# RPlan_LB.net
KiCad netlist of a schematic drawn in Altium Designer
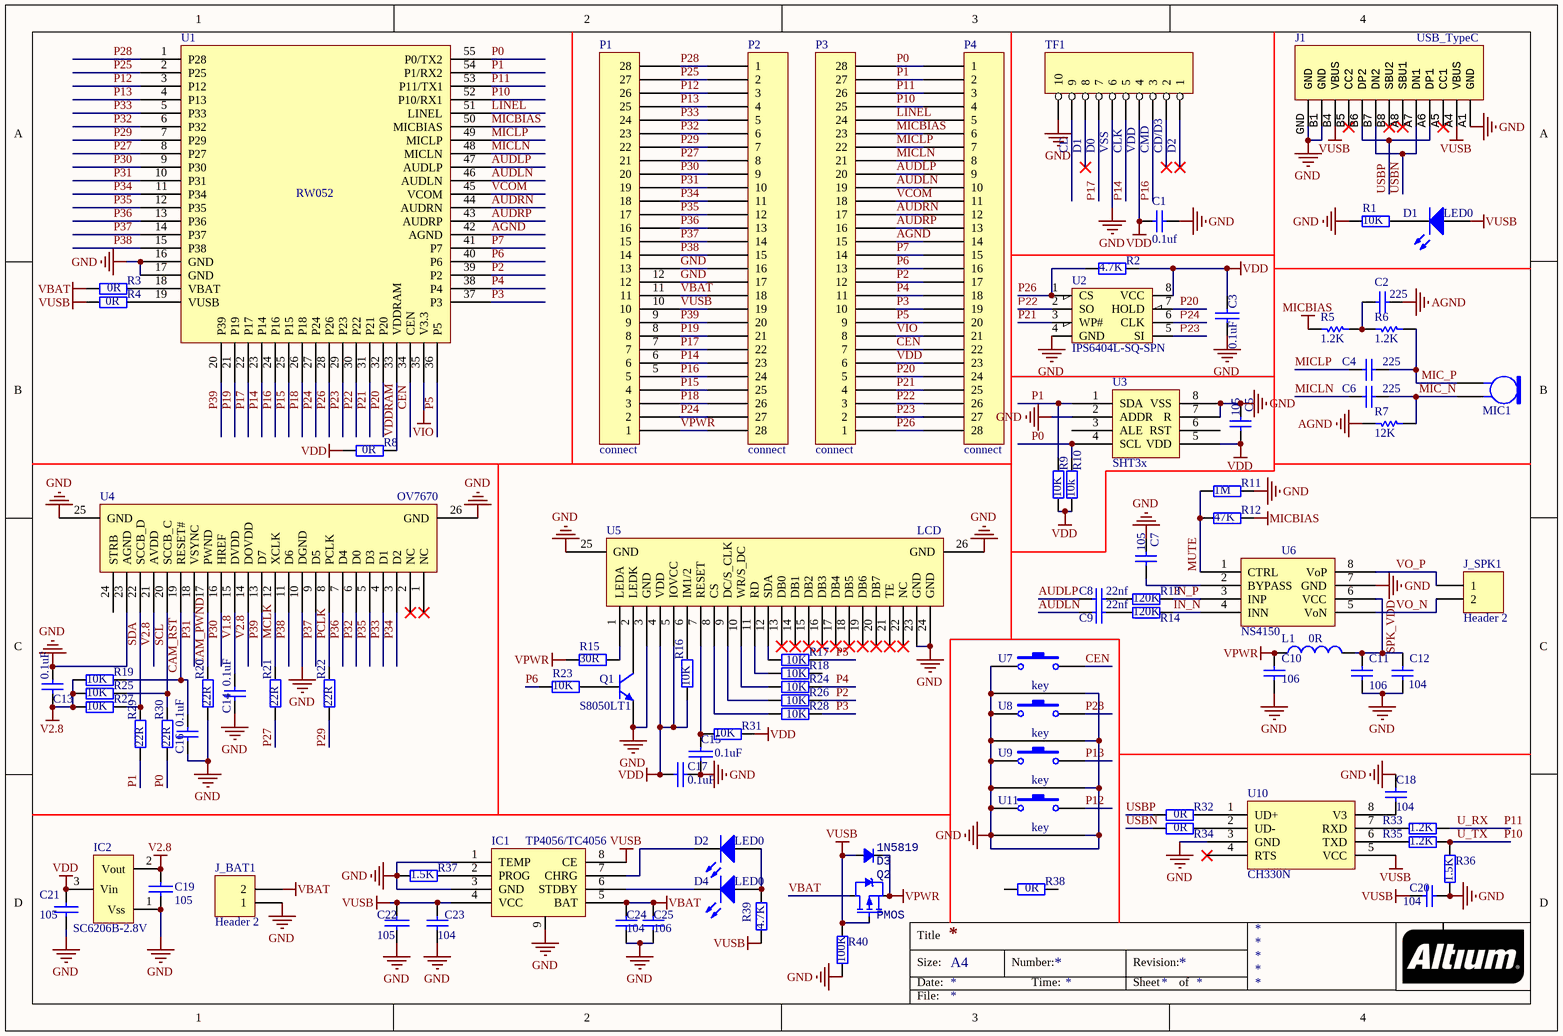
[diagram p0: RPlan_LB.SchDoc]

(export (version "E")
  (design (tool "Eeschema 10.0.6"))
  (components
    (comp (ref "C1")
      (value "0.1uf")
      (footprint "0603C")
      (description "Capacitor")
      (fields (field (name "PUBLISHER") "Altium Limited"))
      (libsource (lib "Miscellaneous Devices") (part "Cap"))
    )
    (comp (ref "C2") (value "225") (footprint "0603C") (libsource (lib "Miscellaneous Gallery") (part "CAP")))
    (comp (ref "C3")
      (value "0.1uF")
      (footprint "0603C")
      (description "Capacitor")
      (libsource (lib "Schlib") (part "CAP"))
    )
    (comp (ref "C4") (value "225") (footprint "0603C") (libsource (lib "Miscellaneous Gallery") (part "CAP")))
    (comp (ref "C5")
      (value "105")
      (footprint "0603C")
      (description "Capacitor")
      (fields (field (name "PUBLISHER") "Altium Limited"))
      (libsource (lib "Miscellaneous Devices") (part "Cap"))
    )
    (comp (ref "C6") (value "225") (footprint "0603C") (libsource (lib "Miscellaneous Gallery") (part "CAP")))
    (comp (ref "C7")
      (value "105")
      (footprint "0603C")
      (description "Capacitor")
      (fields (field (name "PUBLISHER") "Altium Limited"))
      (libsource (lib "Miscellaneous Devices") (part "Cap"))
    )
    (comp (ref "C8")
      (value "22nf")
      (footprint "0603C")
      (description "Capacitor")
      (fields (field (name "PUBLISHER") "Altium Limited"))
      (libsource (lib "") (part "Cap_1"))
    )
    (comp (ref "C9")
      (value "22nf")
      (footprint "0603C")
      (description "Capacitor")
      (fields (field (name "PUBLISHER") "Altium Limited"))
      (libsource (lib "Miscellaneous Devices") (part "Cap"))
    )
    (comp (ref "C10")
      (value "106")
      (footprint "0603C")
      (description "Capacitor")
      (fields (field (name "PUBLISHER") "Altium Limited"))
      (libsource (lib "Miscellaneous Devices") (part "Cap"))
    )
    (comp (ref "C11")
      (value "106")
      (footprint "0603C")
      (description "Capacitor")
      (fields (field (name "PUBLISHER") "Altium Limited"))
      (libsource (lib "Miscellaneous Devices") (part "Cap"))
    )
    (comp (ref "C12")
      (value "104")
      (footprint "0603C")
      (libsource (lib "Miscellaneous Gallery") (part "CAP"))
    )
    (comp (ref "C13")
      (value "0.1uF")
      (footprint "0603C")
      (description "Capacitor")
      (fields (field (name "PUBLISHER") "Altium Limited"))
      (libsource (lib "") (part "Cap_1"))
    )
    (comp (ref "C14")
      (value "0.1uF")
      (footprint "0603C")
      (description "Capacitor")
      (fields (field (name "PUBLISHER") "Altium Limited"))
      (libsource (lib "") (part "Cap_1"))
    )
    (comp (ref "C15")
      (value "0.1uF")
      (footprint "0603C")
      (description "Capacitor")
      (libsource (lib "*") (part "CAP"))
    )
    (comp (ref "C16")
      (value "0.1uF")
      (footprint "0603C")
      (description "Capacitor")
      (fields (field (name "PUBLISHER") "Altium Limited"))
      (libsource (lib "") (part "Cap_1"))
    )
    (comp (ref "C17")
      (value "0.1uF")
      (footprint "0603C")
      (description "Capacitor")
      (libsource (lib "*") (part "CAP"))
    )
    (comp (ref "C18")
      (value "104")
      (footprint "0603C")
      (description "Capacitor")
      (fields (field (name "PUBLISHER") "Altium Limited"))
      (libsource (lib "Miscellaneous Devices") (part "Cap"))
    )
    (comp (ref "C19")
      (value "105")
      (footprint "0603C")
      (description "Capacitor")
      (libsource (lib "*") (part "CAP"))
    )
    (comp (ref "C20")
      (value "104")
      (footprint "0603C")
      (description "Capacitor")
      (fields (field (name "PUBLISHER") "Altium Limited"))
      (libsource (lib "Miscellaneous Devices") (part "Cap"))
    )
    (comp (ref "C21")
      (value "105")
      (footprint "0603C")
      (description "Capacitor")
      (libsource (lib "*") (part "CAP"))
    )
    (comp (ref "C22")
      (value "105")
      (footprint "0603C")
      (description "Capacitor")
      (libsource (lib "Schlib") (part "CAP"))
    )
    (comp (ref "C23")
      (value "104")
      (footprint "0603C")
      (description "Capacitor")
      (fields (field (name "PUBLISHER") "Altium Limited"))
      (libsource (lib "Miscellaneous Devices") (part "Cap"))
    )
    (comp (ref "C24")
      (value "104")
      (footprint "0603C")
      (description "Capacitor")
      (fields (field (name "PUBLISHER") "Altium Limited"))
      (libsource (lib "Miscellaneous Devices") (part "Cap"))
    )
    (comp (ref "C25")
      (value "106")
      (footprint "0603C")
      (description "Capacitor")
      (fields (field (name "PUBLISHER") "Altium Limited"))
      (libsource (lib "Miscellaneous Devices") (part "Cap"))
    )
    (comp (ref "D1")
      (value "LED0")
      (footprint "0603_LED_R")
      (description "Typical INFRARED GaAs LED")
      (fields (field (name "PUBLISHER") "Altium Limited"))
      (libsource (lib "Miscellaneous Devices") (part "LED0"))
    )
    (comp (ref "D2")
      (value "LED0")
      (footprint "0603_LED_R")
      (description "Typical INFRARED GaAs LED")
      (fields (field (name "PUBLISHER") "Altium Limited"))
      (libsource (lib "Miscellaneous Devices") (part "LED0"))
    )
    (comp (ref "D3")
      (value "1N5819")
      (footprint "SOD-323")
      (description "Diode")
      (libsource (lib "Integrated_Library") (part "Diode_SOD123"))
    )
    (comp (ref "D4")
      (value "LED0")
      (footprint "0603_LED_G")
      (description "Typical INFRARED GaAs LED")
      (fields (field (name "PUBLISHER") "Altium Limited"))
      (libsource (lib "Miscellaneous Devices") (part "LED0"))
    )
    (comp (ref "IC1")
      (value "TP4056/TC4056")
      (footprint "SOP8_150mil")
      (libsource (lib "TP4056") (part "4056"))
    )
    (comp (ref "IC2")
      (value "SC6206B-2.8V")
      (footprint "SOT-23-3")
      (description "SC6206B-3V")
      (libsource (lib "Schlib") (part "ME6206A33M3G"))
    )
    (comp (ref "J1")
      (value "USB_TypeC")
      (footprint "USB_TypeC")
      (description "USB")
      (libsource (lib "SCH_USB") (part "USB_TypeC"))
    )
    (comp (ref "J_BAT1")
      (value "Header 2")
      (footprint "BAT")
      (description "Header, 2-Pin")
      (fields (field (name "PUBLISHER") "Altium Limited"))
      (libsource (lib "Miscellaneous Connectors") (part "Header 2"))
    )
    (comp (ref "J_SPK1")
      (value "Header 2")
      (footprint "MIC_4015_DIP")
      (description "Header, 2-Pin")
      (fields (field (name "PUBLISHER") "Altium Limited"))
      (libsource (lib "") (part "Header 2_1"))
    )
    (comp (ref "L1")
      (value "0R")
      (footprint "0603C")
      (description "GZ1608D121TF")
      (fields (field (name "PUBLISHER") "Altium Limited"))
      (libsource (lib "Miscellaneous Devices") (part "Inductor"))
    )
    (comp (ref "MIC1")
      (value "MIC")
      (footprint "MIC_4015_DIP")
      (libsource (lib "Miscellaneous Gallery") (part "MIC"))
    )
    (comp (ref "P1") (value "connect") (footprint "CONNECT2") (libsource (lib "") (part "connect_1")))
    (comp (ref "P2") (value "connect") (footprint "CONNECT") (libsource (lib "") (part "connect_2")))
    (comp (ref "P3") (value "connect") (footprint "CONNECT") (libsource (lib "RPlan_LB") (part "connect")))
    (comp (ref "P4") (value "connect") (footprint "CONNECT2") (libsource (lib "") (part "connect_2")))
    (comp (ref "Q1")
      (value "S8050LT1")
      (footprint "SOT-23-3")
      (description "NPN Bipolar Transistor")
      (fields (field (name "PUBLISHER") "Altium Limited"))
      (libsource (lib "Schlib") (part "NPN"))
    )
    (comp (ref "Q2")
      (value "PMOS")
      (footprint "SOT-23-3")
      (description "MOSFET")
      (libsource (lib "SCH_Active") (part "MOSFET_P_SOT23"))
    )
    (comp (ref "R1")
      (value "10K")
      (footprint "0603C")
      (description "RES")
      (libsource (lib "") (part "RES_1"))
    )
    (comp (ref "R2")
      (value "4.7K")
      (footprint "0603C")
      (description "RES")
      (libsource (lib "") (part "RES_2"))
    )
    (comp (ref "R3")
      (value "0R")
      (footprint "0603C")
      (description "Resistor")
      (fields (field (name "PUBLISHER") "Altium Limited"))
      (libsource (lib "") (part "Res2_1"))
    )
    (comp (ref "R4")
      (value "0R")
      (footprint "0603C")
      (description "Resistor")
      (fields (field (name "PUBLISHER") "Altium Limited"))
      (libsource (lib "") (part "Res2_1"))
    )
    (comp (ref "R5")
      (value "1.2K")
      (footprint "0603C")
      (libsource (lib "Miscellaneous Gallery") (part "Res"))
    )
    (comp (ref "R6") (value "1.2K") (footprint "0603C") (libsource (lib "") (part "Res_1")))
    (comp (ref "R7") (value "12K") (footprint "0603C") (libsource (lib "Miscellaneous Gallery") (part "Res")))
    (comp (ref "R8")
      (value "0R")
      (footprint "0603C")
      (description "Resistor")
      (fields (field (name "PUBLISHER") "Altium Limited"))
      (libsource (lib "") (part "Res2_1"))
    )
    (comp (ref "R9")
      (value "10K")
      (footprint "0603C")
      (description "RES")
      (libsource (lib "Schlib") (part "RES"))
    )
    (comp (ref "R10")
      (value "10k")
      (footprint "0603C")
      (description "RES")
      (libsource (lib "Schlib") (part "RES"))
    )
    (comp (ref "R11")
      (value "1M")
      (footprint "0603C")
      (description "RES")
      (libsource (lib "") (part "RES_1"))
    )
    (comp (ref "R12")
      (value "47K")
      (footprint "0603C")
      (description "RES")
      (libsource (lib "") (part "RES_1"))
    )
    (comp (ref "R13")
      (value "120K")
      (footprint "0603C")
      (description "RES")
      (libsource (lib "") (part "RES_2"))
    )
    (comp (ref "R14")
      (value "120K")
      (footprint "0603C")
      (description "RES")
      (libsource (lib "") (part "RES_1"))
    )
    (comp (ref "R15")
      (value "30R")
      (footprint "0603C")
      (description "Resistor")
      (fields (field (name "PUBLISHER") "Altium Limited"))
      (libsource (lib "") (part "Res2_1"))
    )
    (comp (ref "R16")
      (value "10K")
      (footprint "0603C")
      (description "Resistor")
      (fields (field (name "PUBLISHER") "Altium Limited"))
      (libsource (lib "") (part "Res2_2"))
    )
    (comp (ref "R17")
      (value "10K")
      (footprint "0603C")
      (description "Resistor")
      (fields (field (name "PUBLISHER") "Altium Limited"))
      (libsource (lib "") (part "Res2_1"))
    )
    (comp (ref "R18")
      (value "10K")
      (footprint "0603C")
      (description "Resistor")
      (fields (field (name "PUBLISHER") "Altium Limited"))
      (libsource (lib "") (part "Res2_1"))
    )
    (comp (ref "R19")
      (value "10K")
      (footprint "0603C")
      (description "Resistor")
      (fields (field (name "PUBLISHER") "Altium Limited"))
      (libsource (lib "") (part "Res2_1"))
    )
    (comp (ref "R20")
      (value "22R")
      (footprint "0603C")
      (description "Resistor")
      (fields (field (name "PUBLISHER") "Altium Limited"))
      (libsource (lib "Miscellaneous Devices") (part "Res2"))
    )
    (comp (ref "R21")
      (value "22R")
      (footprint "0603C")
      (description "Resistor")
      (fields (field (name "PUBLISHER") "Altium Limited"))
      (libsource (lib "Miscellaneous Devices") (part "Res2"))
    )
    (comp (ref "R22")
      (value "22R")
      (footprint "0603C")
      (description "Resistor")
      (fields (field (name "PUBLISHER") "Altium Limited"))
      (libsource (lib "") (part "Res2_2"))
    )
    (comp (ref "R23")
      (value "10K")
      (footprint "0603C")
      (description "Resistor")
      (fields (field (name "PUBLISHER") "Altium Limited"))
      (libsource (lib "") (part "Res2_1"))
    )
    (comp (ref "R24")
      (value "10K")
      (footprint "0603C")
      (description "Resistor")
      (fields (field (name "PUBLISHER") "Altium Limited"))
      (libsource (lib "") (part "Res2_1"))
    )
    (comp (ref "R25")
      (value "10K")
      (footprint "0603C")
      (description "Resistor")
      (fields (field (name "PUBLISHER") "Altium Limited"))
      (libsource (lib "") (part "Res2_1"))
    )
    (comp (ref "R26")
      (value "10K")
      (footprint "0603C")
      (description "Resistor")
      (fields (field (name "PUBLISHER") "Altium Limited"))
      (libsource (lib "") (part "Res2_1"))
    )
    (comp (ref "R27")
      (value "10K")
      (footprint "0603C")
      (description "Resistor")
      (fields (field (name "PUBLISHER") "Altium Limited"))
      (libsource (lib "") (part "Res2_1"))
    )
    (comp (ref "R28")
      (value "10K")
      (footprint "0603C")
      (description "Resistor")
      (fields (field (name "PUBLISHER") "Altium Limited"))
      (libsource (lib "") (part "Res2_1"))
    )
    (comp (ref "R29")
      (value "22R")
      (footprint "0603C")
      (description "Resistor")
      (fields (field (name "PUBLISHER") "Altium Limited"))
      (libsource (lib "Miscellaneous Devices") (part "Res2"))
    )
    (comp (ref "R30")
      (value "22R")
      (footprint "0603C")
      (description "Resistor")
      (fields (field (name "PUBLISHER") "Altium Limited"))
      (libsource (lib "Miscellaneous Devices") (part "Res2"))
    )
    (comp (ref "R31")
      (value "10K")
      (footprint "0603C")
      (description "Resistor")
      (fields (field (name "PUBLISHER") "Altium Limited"))
      (libsource (lib "") (part "Res2_1"))
    )
    (comp (ref "R32")
      (value "0R")
      (footprint "0603C")
      (description "RES")
      (libsource (lib "") (part "RES_2"))
    )
    (comp (ref "R33")
      (value "1.2K")
      (footprint "0603C")
      (description "RES")
      (libsource (lib "") (part "RES_2"))
    )
    (comp (ref "R34")
      (value "0R")
      (footprint "0603C")
      (description "RES")
      (libsource (lib "") (part "RES_2"))
    )
    (comp (ref "R35")
      (value "1.2K")
      (footprint "0603C")
      (description "RES")
      (libsource (lib "") (part "RES_2"))
    )
    (comp (ref "R36")
      (value "1.5K")
      (footprint "0603C")
      (description "RES")
      (libsource (lib "") (part "RES_3"))
    )
    (comp (ref "R37")
      (value "1.5K")
      (footprint "0603C")
      (description "RES")
      (libsource (lib "") (part "RES_2"))
    )
    (comp (ref "R38")
      (value "0R")
      (footprint "LCD_13")
      (description "RES")
      (libsource (lib "") (part "RES_2"))
    )
    (comp (ref "R39")
      (value "4.7K")
      (footprint "0603C")
      (description "RES")
      (libsource (lib "Schlib") (part "RES"))
    )
    (comp (ref "R40")
      (value "100K")
      (footprint "0603C")
      (description "RES")
      (libsource (lib "") (part "RES_3"))
    )
    (comp (ref "TF1") (value "~") (footprint "TF1") (libsource (lib "*") (part "HEADER 10")))
    (comp (ref "U1") (value "RW052") (footprint "RW052") (libsource (lib "RW052") (part "RW052")))
    (comp (ref "U2")
      (value "IPS6404L-SQ-SPN")
      (footprint "SOP8_150mil")
      (libsource (lib "Schlib") (part "W25X16"))
    )
    (comp (ref "U3") (value "SHT3x") (footprint "SHT3X") (libsource (lib "RPlan_LB") (part "SHT3x")))
    (comp (ref "U4")
      (value "OV7670")
      (footprint "FPC_0.5_24P_L")
      (libsource (lib "RPlan_LB") (part "OV7670"))
    )
    (comp (ref "U5") (value "LCD") (footprint "FPC_0.5_24P_LF") (libsource (lib "RPlan_LB") (part "LCD")))
    (comp (ref "U6") (value "NS4150") (footprint "SOP8_150mil") (libsource (lib "NS4150") (part "NS4150")))
    (comp (ref "U7") (value "key") (footprint "KEY") (libsource (lib "RPlan_LB") (part "key")))
    (comp (ref "U8") (value "key") (footprint "KEY") (libsource (lib "RPlan_LB") (part "key")))
    (comp (ref "U9") (value "key") (footprint "KEY") (libsource (lib "RPlan_LB") (part "key")))
    (comp (ref "U10")
      (value "CH330N")
      (footprint "SOP8_150mil")
      (libsource (lib "CH330_340") (part "CH330N"))
    )
    (comp (ref "U11") (value "key") (footprint "KEY") (libsource (lib "RPlan_LB") (part "key")))
  )
  (nets
    (net (code "1") (name "/AUDLN") (class "Default")
      (node (ref "C9") (pin "2") (pinfunction "2_2") (pintype "passive"))
      (node (ref "P3") (pin "19") (pinfunction "19_19") (pintype "passive"))
      (node (ref "P4") (pin "10") (pinfunction "10_10") (pintype "passive"))
      (node (ref "U1") (pin "46") (pinfunction "AUDLN_46") (pintype "passive"))
    )
    (net (code "2") (name "/AUDLP") (class "Default")
      (node (ref "C8") (pin "2") (pinfunction "2_2") (pintype "passive"))
      (node (ref "P3") (pin "20") (pinfunction "20_20") (pintype "passive"))
      (node (ref "P4") (pin "9") (pinfunction "9_9") (pintype "passive"))
      (node (ref "U1") (pin "47") (pinfunction "AUDLP_47") (pintype "passive"))
    )
    (net (code "3") (name "/AUDRN") (class "Default")
      (node (ref "P3") (pin "17") (pinfunction "17_17") (pintype "passive"))
      (node (ref "P4") (pin "12") (pinfunction "12_12") (pintype "passive"))
      (node (ref "U1") (pin "44") (pinfunction "AUDRN_44") (pintype "passive"))
    )
    (net (code "4") (name "/AUDRP") (class "Default")
      (node (ref "P3") (pin "16") (pinfunction "16_16") (pintype "passive"))
      (node (ref "P4") (pin "13") (pinfunction "13_13") (pintype "passive"))
      (node (ref "U1") (pin "43") (pinfunction "AUDRP_43") (pintype "passive"))
    )
    (net (code "5") (name "/CAM_PWND") (class "Default")
      (node (ref "R20") (pin "2") (pinfunction "2_2") (pintype "passive"))
      (node (ref "U4") (pin "17") (pinfunction "PWND_17") (pintype "passive"))
    )
    (net (code "6") (name "/CAM_RST") (class "Default")
      (node (ref "C16") (pin "2") (pinfunction "2_2") (pintype "passive"))
      (node (ref "R19") (pin "1") (pinfunction "1_1") (pintype "passive"))
      (node (ref "U4") (pin "19") (pinfunction "RESET#_19") (pintype "passive"))
    )
    (net (code "7") (name "/CEN") (class "Default")
      (node (ref "P3") (pin "7") (pinfunction "7_7") (pintype "passive"))
      (node (ref "P4") (pin "22") (pinfunction "22_22") (pintype "passive"))
      (node (ref "U1") (pin "34") (pinfunction "CEN_34") (pintype "passive"))
      (node (ref "U7") (pin "2") (pinfunction "2_2") (pintype "passive"))
    )
    (net (code "8") (name "/IN_N") (class "Default")
      (node (ref "R14") (pin "2") (pinfunction "2_2") (pintype "passive"))
      (node (ref "U6") (pin "4") (pinfunction "INN_4") (pintype "passive"))
    )
    (net (code "9") (name "/IN_P") (class "Default")
      (node (ref "R13") (pin "1") (pinfunction "1_1") (pintype "passive"))
      (node (ref "U6") (pin "3") (pinfunction "INP_3") (pintype "passive"))
    )
    (net (code "10") (name "/LINEL") (class "Default")
      (node (ref "P3") (pin "24") (pinfunction "24_24") (pintype "passive"))
      (node (ref "P4") (pin "5") (pinfunction "5_5") (pintype "passive"))
      (node (ref "U1") (pin "51") (pinfunction "LINEL_51") (pintype "passive"))
    )
    (net (code "11") (name "/MCLK") (class "Default")
      (node (ref "R21") (pin "2") (pinfunction "2_2") (pintype "passive"))
      (node (ref "U4") (pin "12") (pinfunction "XCLK_12") (pintype "passive"))
    )
    (net (code "12") (name "/MICLN") (class "Default")
      (node (ref "C6") (pin "2") (pinfunction "2_2") (pintype "passive"))
      (node (ref "P3") (pin "21") (pinfunction "21_21") (pintype "passive"))
      (node (ref "P4") (pin "8") (pinfunction "8_8") (pintype "passive"))
      (node (ref "U1") (pin "48") (pinfunction "MICLN_48") (pintype "passive"))
    )
    (net (code "13") (name "/MICLP") (class "Default")
      (node (ref "C4") (pin "2") (pinfunction "2_2") (pintype "passive"))
      (node (ref "P3") (pin "22") (pinfunction "22_22") (pintype "passive"))
      (node (ref "P4") (pin "7") (pinfunction "7_7") (pintype "passive"))
      (node (ref "U1") (pin "49") (pinfunction "MICLP_49") (pintype "passive"))
    )
    (net (code "14") (name "/MIC_N") (class "Default")
      (node (ref "C6") (pin "1") (pinfunction "1_1") (pintype "passive"))
      (node (ref "MIC1") (pin "2") (pinfunction "2_2") (pintype "passive"))
      (node (ref "R7") (pin "2") (pinfunction "2_2") (pintype "passive"))
    )
    (net (code "15") (name "/MIC_P") (class "Default")
      (node (ref "C4") (pin "1") (pinfunction "1_1") (pintype "passive"))
      (node (ref "MIC1") (pin "1") (pinfunction "1_1") (pintype "passive"))
      (node (ref "R6") (pin "1") (pinfunction "1_1") (pintype "passive"))
    )
    (net (code "16") (name "/MUTE") (class "Default")
      (node (ref "R11") (pin "1") (pinfunction "1_1") (pintype "passive"))
      (node (ref "R12") (pin "1") (pinfunction "1_1") (pintype "passive"))
      (node (ref "U6") (pin "1") (pinfunction "CTRL_1") (pintype "passive"))
    )
    (net (code "17") (name "/P0") (class "Default")
      (node (ref "P3") (pin "28") (pinfunction "28_28") (pintype "passive"))
      (node (ref "P4") (pin "1") (pinfunction "1_1") (pintype "passive"))
      (node (ref "R10") (pin "1") (pinfunction "1_1") (pintype "passive"))
      (node (ref "R30") (pin "1") (pinfunction "1_1") (pintype "passive"))
      (node (ref "U1") (pin "55") (pinfunction "P0/TX2_55") (pintype "passive"))
      (node (ref "U3") (pin "4") (pinfunction "SCL_4") (pintype "passive"))
    )
    (net (code "18") (name "/P1") (class "Default")
      (node (ref "P3") (pin "27") (pinfunction "27_27") (pintype "passive"))
      (node (ref "P4") (pin "2") (pinfunction "2_2") (pintype "passive"))
      (node (ref "R29") (pin "1") (pinfunction "1_1") (pintype "passive"))
      (node (ref "R9") (pin "1") (pinfunction "1_1") (pintype "passive"))
      (node (ref "U1") (pin "54") (pinfunction "P1/RX2_54") (pintype "passive"))
      (node (ref "U3") (pin "1") (pinfunction "SDA_1") (pintype "passive"))
    )
    (net (code "19") (name "/P2") (class "Default")
      (node (ref "P3") (pin "12") (pinfunction "12_12") (pintype "passive"))
      (node (ref "P4") (pin "17") (pinfunction "17_17") (pintype "passive"))
      (node (ref "R26") (pin "1") (pinfunction "1_1") (pintype "passive"))
      (node (ref "U1") (pin "39") (pinfunction "P2_39") (pintype "passive"))
    )
    (net (code "20") (name "/P3") (class "Default")
      (node (ref "P3") (pin "10") (pinfunction "10_10") (pintype "passive"))
      (node (ref "P4") (pin "19") (pinfunction "19_19") (pintype "passive"))
      (node (ref "R28") (pin "1") (pinfunction "1_1") (pintype "passive"))
      (node (ref "U1") (pin "37") (pinfunction "P3_37") (pintype "passive"))
    )
    (net (code "21") (name "/P4") (class "Default")
      (node (ref "P3") (pin "11") (pinfunction "11_11") (pintype "passive"))
      (node (ref "P4") (pin "18") (pinfunction "18_18") (pintype "passive"))
      (node (ref "R24") (pin "1") (pinfunction "1_1") (pintype "passive"))
      (node (ref "U1") (pin "38") (pinfunction "P4_38") (pintype "passive"))
    )
    (net (code "22") (name "/P5") (class "Default")
      (node (ref "P3") (pin "9") (pinfunction "9_9") (pintype "passive"))
      (node (ref "P4") (pin "20") (pinfunction "20_20") (pintype "passive"))
      (node (ref "R17") (pin "1") (pinfunction "1_1") (pintype "passive"))
      (node (ref "U1") (pin "36") (pinfunction "P5_36") (pintype "passive"))
    )
    (net (code "23") (name "/P6") (class "Default")
      (node (ref "P3") (pin "13") (pinfunction "13_13") (pintype "passive"))
      (node (ref "P4") (pin "16") (pinfunction "16_16") (pintype "passive"))
      (node (ref "R23") (pin "2") (pinfunction "2_2") (pintype "passive"))
      (node (ref "U1") (pin "40") (pinfunction "P6_40") (pintype "passive"))
    )
    (net (code "24") (name "/P7") (class "Default")
      (node (ref "P3") (pin "14") (pinfunction "14_14") (pintype "passive"))
      (node (ref "P4") (pin "15") (pinfunction "15_15") (pintype "passive"))
      (node (ref "U1") (pin "41") (pinfunction "P7_41") (pintype "passive"))
    )
    (net (code "25") (name "/P10") (class "Default")
      (node (ref "P3") (pin "25") (pinfunction "25_25") (pintype "passive"))
      (node (ref "P4") (pin "4") (pinfunction "4_4") (pintype "passive"))
      (node (ref "R35") (pin "1") (pinfunction "1_1") (pintype "passive"))
      (node (ref "R36") (pin "2") (pinfunction "2_2") (pintype "passive"))
      (node (ref "U1") (pin "52") (pinfunction "P10/RX1_52") (pintype "passive"))
    )
    (net (code "26") (name "/P11") (class "Default")
      (node (ref "P3") (pin "26") (pinfunction "26_26") (pintype "passive"))
      (node (ref "P4") (pin "3") (pinfunction "3_3") (pintype "passive"))
      (node (ref "R33") (pin "1") (pinfunction "1_1") (pintype "passive"))
      (node (ref "U1") (pin "53") (pinfunction "P11/TX1_53") (pintype "passive"))
    )
    (net (code "27") (name "/P12") (class "Default")
      (node (ref "P1") (pin "26") (pinfunction "26_26") (pintype "passive"))
      (node (ref "P2") (pin "3") (pinfunction "3_3") (pintype "passive"))
      (node (ref "U1") (pin "3") (pinfunction "P12_3") (pintype "passive"))
      (node (ref "U11") (pin "2") (pinfunction "2_2") (pintype "passive"))
    )
    (net (code "28") (name "/P13") (class "Default")
      (node (ref "P1") (pin "25") (pinfunction "25_25") (pintype "passive"))
      (node (ref "P2") (pin "4") (pinfunction "4_4") (pintype "passive"))
      (node (ref "U1") (pin "4") (pinfunction "P13_4") (pintype "passive"))
      (node (ref "U9") (pin "2") (pinfunction "2_2") (pintype "passive"))
    )
    (net (code "29") (name "/P14") (class "Default")
      (node (ref "P1") (pin "6") (pinfunction "6_6") (pintype "passive"))
      (node (ref "P2") (pin "23") (pinfunction "23_23") (pintype "passive"))
      (node (ref "TF1") (pin "5") (pinfunction "5_5") (pintype "passive"))
      (node (ref "U1") (pin "23") (pinfunction "P14_23") (pintype "passive"))
    )
    (net (code "30") (name "/P15") (class "Default")
      (node (ref "P1") (pin "4") (pinfunction "4_4") (pintype "passive"))
      (node (ref "P2") (pin "25") (pinfunction "25_25") (pintype "passive"))
      (node (ref "U1") (pin "25") (pinfunction "P15_25") (pintype "passive"))
    )
    (net (code "31") (name "/P16") (class "Default")
      (node (ref "P1") (pin "5") (pinfunction "5_5") (pintype "passive"))
      (node (ref "P2") (pin "24") (pinfunction "24_24") (pintype "passive"))
      (node (ref "TF1") (pin "3") (pinfunction "3_3") (pintype "passive"))
      (node (ref "U1") (pin "24") (pinfunction "P16_24") (pintype "passive"))
    )
    (net (code "32") (name "/P17") (class "Default")
      (node (ref "P1") (pin "7") (pinfunction "7_7") (pintype "passive"))
      (node (ref "P2") (pin "22") (pinfunction "22_22") (pintype "passive"))
      (node (ref "TF1") (pin "7") (pinfunction "7_7") (pintype "passive"))
      (node (ref "U1") (pin "22") (pinfunction "P17_22") (pintype "passive"))
    )
    (net (code "33") (name "/P18") (class "Default")
      (node (ref "P1") (pin "3") (pinfunction "3_3") (pintype "passive"))
      (node (ref "P2") (pin "26") (pinfunction "26_26") (pintype "passive"))
      (node (ref "U1") (pin "26") (pinfunction "P18_26") (pintype "passive"))
    )
    (net (code "34") (name "/P19") (class "Default")
      (node (ref "P1") (pin "8") (pinfunction "8_8") (pintype "passive"))
      (node (ref "P2") (pin "21") (pinfunction "21_21") (pintype "passive"))
      (node (ref "U1") (pin "21") (pinfunction "P19_21") (pintype "passive"))
    )
    (net (code "35") (name "/P20") (class "Default")
      (node (ref "P3") (pin "5") (pinfunction "5_5") (pintype "passive"))
      (node (ref "P4") (pin "24") (pinfunction "24_24") (pintype "passive"))
      (node (ref "U1") (pin "32") (pinfunction "P20_32") (pintype "passive"))
      (node (ref "U2") (pin "7") (pinfunction "HOLD_7") (pintype "passive"))
    )
    (net (code "36") (name "/P21") (class "Default")
      (node (ref "P3") (pin "4") (pinfunction "4_4") (pintype "passive"))
      (node (ref "P4") (pin "25") (pinfunction "25_25") (pintype "passive"))
      (node (ref "U1") (pin "31") (pinfunction "P21_31") (pintype "passive"))
      (node (ref "U2") (pin "3") (pinfunction "WP#_3") (pintype "passive"))
    )
    (net (code "37") (name "/P22") (class "Default")
      (node (ref "P3") (pin "3") (pinfunction "3_3") (pintype "passive"))
      (node (ref "P4") (pin "26") (pinfunction "26_26") (pintype "passive"))
      (node (ref "U1") (pin "30") (pinfunction "P22_30") (pintype "passive"))
      (node (ref "U2") (pin "2") (pinfunction "SO_2") (pintype "passive"))
    )
    (net (code "38") (name "/P23") (class "Default")
      (node (ref "P3") (pin "2") (pinfunction "2_2") (pintype "passive"))
      (node (ref "P4") (pin "27") (pinfunction "27_27") (pintype "passive"))
      (node (ref "U1") (pin "29") (pinfunction "P23_29") (pintype "passive"))
      (node (ref "U2") (pin "5") (pinfunction "SI_5") (pintype "passive"))
    )
    (net (code "39") (name "/P24") (class "Default")
      (node (ref "P1") (pin "2") (pinfunction "2_2") (pintype "passive"))
      (node (ref "P2") (pin "27") (pinfunction "27_27") (pintype "passive"))
      (node (ref "U1") (pin "27") (pinfunction "P24_27") (pintype "passive"))
      (node (ref "U2") (pin "6") (pinfunction "CLK_6") (pintype "passive"))
    )
    (net (code "40") (name "/P25") (class "Default")
      (node (ref "P1") (pin "27") (pinfunction "27_27") (pintype "passive"))
      (node (ref "P2") (pin "2") (pinfunction "2_2") (pintype "passive"))
      (node (ref "U1") (pin "2") (pinfunction "P25_2") (pintype "passive"))
    )
    (net (code "41") (name "/P26") (class "Default")
      (node (ref "P3") (pin "1") (pinfunction "1_1") (pintype "passive"))
      (node (ref "P4") (pin "28") (pinfunction "28_28") (pintype "passive"))
      (node (ref "R2") (pin "2") (pinfunction "2_2") (pintype "passive"))
      (node (ref "U1") (pin "28") (pinfunction "P26_28") (pintype "passive"))
      (node (ref "U2") (pin "1") (pinfunction "CS_1") (pintype "passive"))
    )
    (net (code "42") (name "/P27") (class "Default")
      (node (ref "P1") (pin "21") (pinfunction "21_21") (pintype "passive"))
      (node (ref "P2") (pin "8") (pinfunction "8_8") (pintype "passive"))
      (node (ref "R21") (pin "1") (pinfunction "1_1") (pintype "passive"))
      (node (ref "U1") (pin "8") (pinfunction "P27_8") (pintype "passive"))
    )
    (net (code "43") (name "/P28") (class "Default")
      (node (ref "P1") (pin "28") (pinfunction "28_28") (pintype "passive"))
      (node (ref "P2") (pin "1") (pinfunction "1_1") (pintype "passive"))
      (node (ref "U1") (pin "1") (pinfunction "P28_1") (pintype "passive"))
      (node (ref "U8") (pin "2") (pinfunction "2_2") (pintype "passive"))
    )
    (net (code "44") (name "/P29") (class "Default")
      (node (ref "P1") (pin "22") (pinfunction "22_22") (pintype "passive"))
      (node (ref "P2") (pin "7") (pinfunction "7_7") (pintype "passive"))
      (node (ref "R22") (pin "2") (pinfunction "2_2") (pintype "passive"))
      (node (ref "U1") (pin "7") (pinfunction "P29_7") (pintype "passive"))
    )
    (net (code "45") (name "/P30") (class "Default")
      (node (ref "P1") (pin "20") (pinfunction "20_20") (pintype "passive"))
      (node (ref "P2") (pin "9") (pinfunction "9_9") (pintype "passive"))
      (node (ref "U1") (pin "9") (pinfunction "P30_9") (pintype "passive"))
      (node (ref "U4") (pin "16") (pinfunction "HREF_16") (pintype "passive"))
    )
    (net (code "46") (name "/P31") (class "Default")
      (node (ref "P1") (pin "19") (pinfunction "19_19") (pintype "passive"))
      (node (ref "P2") (pin "10") (pinfunction "10_10") (pintype "passive"))
      (node (ref "U1") (pin "10") (pinfunction "P31_10") (pintype "passive"))
      (node (ref "U4") (pin "18") (pinfunction "VSYNC_18") (pintype "passive"))
    )
    (net (code "47") (name "/P32") (class "Default")
      (node (ref "P1") (pin "23") (pinfunction "23_23") (pintype "passive"))
      (node (ref "P2") (pin "6") (pinfunction "6_6") (pintype "passive"))
      (node (ref "U1") (pin "6") (pinfunction "P32_6") (pintype "passive"))
      (node (ref "U4") (pin "6") (pinfunction "D0_6") (pintype "passive"))
    )
    (net (code "48") (name "/P33") (class "Default")
      (node (ref "P1") (pin "24") (pinfunction "24_24") (pintype "passive"))
      (node (ref "P2") (pin "5") (pinfunction "5_5") (pintype "passive"))
      (node (ref "U1") (pin "5") (pinfunction "P33_5") (pintype "passive"))
      (node (ref "U4") (pin "4") (pinfunction "D1_4") (pintype "passive"))
    )
    (net (code "49") (name "/P34") (class "Default")
      (node (ref "P1") (pin "18") (pinfunction "18_18") (pintype "passive"))
      (node (ref "P2") (pin "11") (pinfunction "11_11") (pintype "passive"))
      (node (ref "U1") (pin "11") (pinfunction "P34_11") (pintype "passive"))
      (node (ref "U4") (pin "3") (pinfunction "D2_3") (pintype "passive"))
    )
    (net (code "50") (name "/P35") (class "Default")
      (node (ref "P1") (pin "17") (pinfunction "17_17") (pintype "passive"))
      (node (ref "P2") (pin "12") (pinfunction "12_12") (pintype "passive"))
      (node (ref "U1") (pin "12") (pinfunction "P35_12") (pintype "passive"))
      (node (ref "U4") (pin "5") (pinfunction "D3_5") (pintype "passive"))
    )
    (net (code "51") (name "/P36") (class "Default")
      (node (ref "P1") (pin "16") (pinfunction "16_16") (pintype "passive"))
      (node (ref "P2") (pin "13") (pinfunction "13_13") (pintype "passive"))
      (node (ref "U1") (pin "13") (pinfunction "P36_13") (pintype "passive"))
      (node (ref "U4") (pin "7") (pinfunction "D4_7") (pintype "passive"))
    )
    (net (code "52") (name "/P37") (class "Default")
      (node (ref "P1") (pin "15") (pinfunction "15_15") (pintype "passive"))
      (node (ref "P2") (pin "14") (pinfunction "14_14") (pintype "passive"))
      (node (ref "U1") (pin "14") (pinfunction "P37_14") (pintype "passive"))
      (node (ref "U4") (pin "9") (pinfunction "D5_9") (pintype "passive"))
    )
    (net (code "53") (name "/P38") (class "Default")
      (node (ref "P1") (pin "14") (pinfunction "14_14") (pintype "passive"))
      (node (ref "P2") (pin "15") (pinfunction "15_15") (pintype "passive"))
      (node (ref "U1") (pin "15") (pinfunction "P38_15") (pintype "passive"))
      (node (ref "U4") (pin "11") (pinfunction "D6_11") (pintype "passive"))
    )
    (net (code "54") (name "/P39") (class "Default")
      (node (ref "P1") (pin "9") (pinfunction "9_9") (pintype "passive"))
      (node (ref "P2") (pin "20") (pinfunction "20_20") (pintype "passive"))
      (node (ref "U1") (pin "20") (pinfunction "P39_20") (pintype "passive"))
      (node (ref "U4") (pin "13") (pinfunction "D7_13") (pintype "passive"))
    )
    (net (code "55") (name "/PCLK") (class "Default")
      (node (ref "R22") (pin "1") (pinfunction "1_1") (pintype "passive"))
      (node (ref "U4") (pin "8") (pinfunction "PCLK_8") (pintype "passive"))
    )
    (net (code "56") (name "/SCL") (class "Default")
      (node (ref "R25") (pin "1") (pinfunction "1_1") (pintype "passive"))
      (node (ref "R30") (pin "2") (pinfunction "2_2") (pintype "passive"))
      (node (ref "U4") (pin "20") (pinfunction "SCCB_C_20") (pintype "passive"))
    )
    (net (code "57") (name "/SDA") (class "Default")
      (node (ref "R27") (pin "1") (pinfunction "1_1") (pintype "passive"))
      (node (ref "R29") (pin "2") (pinfunction "2_2") (pintype "passive"))
      (node (ref "U4") (pin "22") (pinfunction "SCCB_D_22") (pintype "passive"))
    )
    (net (code "58") (name "/SPK_VDD") (class "Default")
      (node (ref "C11") (pin "1") (pinfunction "1_1") (pintype "passive"))
      (node (ref "C12") (pin "2") (pinfunction "2_2") (pintype "passive"))
      (node (ref "L1") (pin "2") (pinfunction "2_2") (pintype "passive"))
      (node (ref "U6") (pin "6") (pinfunction "VCC_6") (pintype "passive"))
    )
    (net (code "59") (name "/USBN") (class "Default")
      (node (ref "J1") (pin "A7") (pinfunction "DN1_A7") (pintype "passive"))
      (node (ref "J1") (pin "B7") (pinfunction "DN2_B7") (pintype "passive"))
      (node (ref "R34") (pin "2") (pinfunction "2_2") (pintype "passive"))
    )
    (net (code "60") (name "/USBP") (class "Default")
      (node (ref "J1") (pin "A6") (pinfunction "DP1_A6") (pintype "passive"))
      (node (ref "J1") (pin "B6") (pinfunction "DP2_B6") (pintype "passive"))
      (node (ref "R32") (pin "2") (pinfunction "2_2") (pintype "passive"))
    )
    (net (code "61") (name "/V1.8") (class "Default")
      (node (ref "C14") (pin "2") (pinfunction "2_2") (pintype "passive"))
      (node (ref "U4") (pin "15") (pinfunction "DVDD_15") (pintype "passive"))
    )
    (net (code "62") (name "/VCOM") (class "Default")
      (node (ref "P3") (pin "18") (pinfunction "18_18") (pintype "passive"))
      (node (ref "P4") (pin "11") (pinfunction "11_11") (pintype "passive"))
      (node (ref "U1") (pin "45") (pinfunction "VCOM_45") (pintype "passive"))
    )
    (net (code "63") (name "/VDDRAM") (class "Default")
      (node (ref "R8") (pin "1") (pinfunction "1_1") (pintype "passive"))
      (node (ref "U1") (pin "33") (pinfunction "VDDRAM_33") (pintype "passive"))
    )
    (net (code "64") (name "/VO_N") (class "Default")
      (node (ref "J_SPK1") (pin "2") (pinfunction "2_2") (pintype "passive"))
      (node (ref "U6") (pin "5") (pinfunction "VoN_5") (pintype "passive"))
    )
    (net (code "65") (name "/VO_P") (class "Default")
      (node (ref "J_SPK1") (pin "1") (pinfunction "1_1") (pintype "passive"))
      (node (ref "U6") (pin "8") (pinfunction "VoP_8") (pintype "passive"))
    )
    (net (code "66") (name "AGND") (class "Default")
      (node (ref "C2") (pin "2") (pinfunction "2_2") (pintype "passive"))
      (node (ref "P3") (pin "15") (pinfunction "15_15") (pintype "passive"))
      (node (ref "P4") (pin "14") (pinfunction "14_14") (pintype "passive"))
      (node (ref "R7") (pin "1") (pinfunction "1_1") (pintype "passive"))
      (node (ref "U1") (pin "42") (pinfunction "AGND_42") (pintype "passive"))
    )
    (net (code "67") (name "GND") (class "Default")
      (node (ref "C1") (pin "2") (pinfunction "2_2") (pintype "passive"))
      (node (ref "C10") (pin "2") (pinfunction "2_2") (pintype "passive"))
      (node (ref "C11") (pin "2") (pinfunction "2_2") (pintype "passive"))
      (node (ref "C12") (pin "1") (pinfunction "1_1") (pintype "passive"))
      (node (ref "C13") (pin "2") (pinfunction "2_2") (pintype "passive"))
      (node (ref "C14") (pin "1") (pinfunction "1_1") (pintype "passive"))
      (node (ref "C15") (pin "1") (pinfunction "1_1") (pintype "passive"))
      (node (ref "C16") (pin "1") (pinfunction "1_1") (pintype "passive"))
      (node (ref "C17") (pin "2") (pinfunction "2_2") (pintype "passive"))
      (node (ref "C18") (pin "2") (pinfunction "2_2") (pintype "passive"))
      (node (ref "C19") (pin "2") (pinfunction "2_2") (pintype "passive"))
      (node (ref "C20") (pin "2") (pinfunction "2_2") (pintype "passive"))
      (node (ref "C21") (pin "2") (pinfunction "2_2") (pintype "passive"))
      (node (ref "C22") (pin "1") (pinfunction "1_1") (pintype "passive"))
      (node (ref "C23") (pin "2") (pinfunction "2_2") (pintype "passive"))
      (node (ref "C24") (pin "2") (pinfunction "2_2") (pintype "passive"))
      (node (ref "C25") (pin "1") (pinfunction "1_1") (pintype "passive"))
      (node (ref "C3") (pin "1") (pinfunction "1_1") (pintype "passive"))
      (node (ref "C5") (pin "2") (pinfunction "2_2") (pintype "passive"))
      (node (ref "C7") (pin "2") (pinfunction "2_2") (pintype "passive"))
      (node (ref "IC1") (pin "1") (pinfunction "TEMP_1") (pintype "passive"))
      (node (ref "IC1") (pin "3") (pinfunction "GND_3") (pintype "passive"))
      (node (ref "IC1") (pin "9") (pinfunction "PAD_9") (pintype "passive"))
      (node (ref "IC2") (pin "1") (pinfunction "Vss_1") (pintype "passive"))
      (node (ref "J1") (pin "A1") (pinfunction "GND_A1") (pintype "power_in"))
      (node (ref "J1") (pin "B1") (pinfunction "GND_B1") (pintype "power_in"))
      (node (ref "J1") (pin "GND") (pinfunction "GND_GND") (pintype "power_in"))
      (node (ref "J_BAT1") (pin "1") (pinfunction "1_1") (pintype "passive"))
      (node (ref "P1") (pin "12") (pinfunction "12_12") (pintype "passive"))
      (node (ref "P1") (pin "13") (pinfunction "13_13") (pintype "passive"))
      (node (ref "P2") (pin "16") (pinfunction "16_16") (pintype "passive"))
      (node (ref "P2") (pin "17") (pinfunction "17_17") (pintype "passive"))
      (node (ref "Q1") (pin "2") (pinfunction "E_2") (pintype "passive"))
      (node (ref "R1") (pin "1") (pinfunction "1_1") (pintype "passive"))
      (node (ref "R11") (pin "2") (pinfunction "2_2") (pintype "passive"))
      (node (ref "R20") (pin "1") (pinfunction "1_1") (pintype "passive"))
      (node (ref "R36") (pin "1") (pinfunction "1_1") (pintype "passive"))
      (node (ref "R37") (pin "2") (pinfunction "2_2") (pintype "passive"))
      (node (ref "R40") (pin "1") (pinfunction "1_1") (pintype "passive"))
      (node (ref "TF1") (pin "10") (pinfunction "10_10") (pintype "passive"))
      (node (ref "TF1") (pin "6") (pinfunction "6_6") (pintype "passive"))
      (node (ref "U1") (pin "16") (pinfunction "GND_16") (pintype "passive"))
      (node (ref "U1") (pin "17") (pinfunction "GND_17") (pintype "passive"))
      (node (ref "U10") (pin "3") (pinfunction "GND_3") (pintype "passive"))
      (node (ref "U11") (pin "1") (pinfunction "1_1") (pintype "passive"))
      (node (ref "U11") (pin "3") (pinfunction "3_3") (pintype "passive"))
      (node (ref "U11") (pin "4") (pinfunction "4_4") (pintype "passive"))
      (node (ref "U2") (pin "4") (pinfunction "GND_4") (pintype "passive"))
      (node (ref "U3") (pin "2") (pinfunction "ADDR_2") (pintype "passive"))
      (node (ref "U3") (pin "7") (pinfunction "R_7") (pintype "passive"))
      (node (ref "U3") (pin "8") (pinfunction "VSS_8") (pintype "passive"))
      (node (ref "U4") (pin "10") (pinfunction "DGND_10") (pintype "passive"))
      (node (ref "U4") (pin "23") (pinfunction "AGND_23") (pintype "passive"))
      (node (ref "U4") (pin "25") (pinfunction "GND_25") (pintype "passive"))
      (node (ref "U4") (pin "26") (pinfunction "GND_26") (pintype "passive"))
      (node (ref "U5") (pin "23") (pinfunction "GND_23") (pintype "passive"))
      (node (ref "U5") (pin "24") (pinfunction "GND_24") (pintype "passive"))
      (node (ref "U5") (pin "25") (pinfunction "GND_25") (pintype "passive"))
      (node (ref "U5") (pin "26") (pinfunction "GND_26") (pintype "passive"))
      (node (ref "U5") (pin "3") (pinfunction "GND_3") (pintype "passive"))
      (node (ref "U6") (pin "7") (pinfunction "GND_7") (pintype "passive"))
      (node (ref "U7") (pin "1") (pinfunction "1_1") (pintype "passive"))
      (node (ref "U7") (pin "3") (pinfunction "3_3") (pintype "passive"))
      (node (ref "U7") (pin "4") (pinfunction "4_4") (pintype "passive"))
      (node (ref "U8") (pin "1") (pinfunction "1_1") (pintype "passive"))
      (node (ref "U8") (pin "3") (pinfunction "3_3") (pintype "passive"))
      (node (ref "U8") (pin "4") (pinfunction "4_4") (pintype "passive"))
      (node (ref "U9") (pin "1") (pinfunction "1_1") (pintype "passive"))
      (node (ref "U9") (pin "3") (pinfunction "3_3") (pintype "passive"))
      (node (ref "U9") (pin "4") (pinfunction "4_4") (pintype "passive"))
    )
    (net (code "68") (name "MICBIAS") (class "Default")
      (node (ref "P3") (pin "23") (pinfunction "23_23") (pintype "passive"))
      (node (ref "P4") (pin "6") (pinfunction "6_6") (pintype "passive"))
      (node (ref "R12") (pin "2") (pinfunction "2_2") (pintype "passive"))
      (node (ref "R5") (pin "1") (pinfunction "1_1") (pintype "passive"))
      (node (ref "U1") (pin "50") (pinfunction "MICBIAS_50") (pintype "passive"))
    )
    (net (code "69") (name "Net-(C2-Pad1)") (class "Default")
      (node (ref "C2") (pin "1") (pinfunction "1_1") (pintype "passive"))
      (node (ref "R5") (pin "2") (pinfunction "2_2") (pintype "passive"))
      (node (ref "R6") (pin "2") (pinfunction "2_2") (pintype "passive"))
    )
    (net (code "70") (name "Net-(C8-Pad1)") (class "Default")
      (node (ref "C8") (pin "1") (pinfunction "1_1") (pintype "passive"))
      (node (ref "R13") (pin "2") (pinfunction "2_2") (pintype "passive"))
    )
    (net (code "71") (name "Net-(C9-Pad1)") (class "Default")
      (node (ref "C9") (pin "1") (pinfunction "1_1") (pintype "passive"))
      (node (ref "R14") (pin "1") (pinfunction "1_1") (pintype "passive"))
    )
    (net (code "72") (name "Net-(D1-K)") (class "Default")
      (node (ref "D1") (pin "2") (pinfunction "K_2") (pintype "passive"))
      (node (ref "R1") (pin "2") (pinfunction "2_2") (pintype "passive"))
    )
    (net (code "73") (name "Net-(D2-A)") (class "Default")
      (node (ref "D2") (pin "1") (pinfunction "A_1") (pintype "passive"))
      (node (ref "D4") (pin "1") (pinfunction "A_1") (pintype "passive"))
      (node (ref "R39") (pin "1") (pinfunction "1_1") (pintype "passive"))
    )
    (net (code "74") (name "Net-(D2-K)") (class "Default")
      (node (ref "D2") (pin "2") (pinfunction "K_2") (pintype "passive"))
      (node (ref "IC1") (pin "7") (pinfunction "CHRG_7") (pintype "passive"))
    )
    (net (code "75") (name "Net-(D4-K)") (class "Default")
      (node (ref "D4") (pin "2") (pinfunction "K_2") (pintype "passive"))
      (node (ref "IC1") (pin "6") (pinfunction "STDBY_6") (pintype "passive"))
    )
    (net (code "76") (name "Net-(IC1-PROG)") (class "Default")
      (node (ref "IC1") (pin "2") (pinfunction "PROG_2") (pintype "passive"))
      (node (ref "R37") (pin "1") (pinfunction "1_1") (pintype "passive"))
    )
    (net (code "77") (name "Net-(Q1-B)") (class "Default")
      (node (ref "Q1") (pin "1") (pinfunction "B_1") (pintype "passive"))
      (node (ref "R23") (pin "1") (pinfunction "1_1") (pintype "passive"))
    )
    (net (code "78") (name "Net-(Q1-C)") (class "Default")
      (node (ref "Q1") (pin "3") (pinfunction "C_3") (pintype "passive"))
      (node (ref "U5") (pin "2") (pinfunction "LEDK_2") (pintype "passive"))
    )
    (net (code "79") (name "Net-(U1-VBAT)") (class "Default")
      (node (ref "R3") (pin "1") (pinfunction "1_1") (pintype "passive"))
      (node (ref "U1") (pin "18") (pinfunction "VBAT_18") (pintype "passive"))
    )
    (net (code "80") (name "Net-(U1-VUSB)") (class "Default")
      (node (ref "R4") (pin "1") (pinfunction "1_1") (pintype "passive"))
      (node (ref "U1") (pin "19") (pinfunction "VUSB_19") (pintype "passive"))
    )
    (net (code "81") (name "Net-(U5-CS)") (class "Default")
      (node (ref "R28") (pin "2") (pinfunction "2_2") (pintype "passive"))
      (node (ref "U5") (pin "8") (pinfunction "CS_8") (pintype "passive"))
    )
    (net (code "82") (name "Net-(U5-DC{slash}S_CLK)") (class "Default")
      (node (ref "R26") (pin "2") (pinfunction "2_2") (pintype "passive"))
      (node (ref "U5") (pin "9") (pinfunction "DC/S_CLK_9") (pintype "passive"))
    )
    (net (code "83") (name "Net-(U5-IM1{slash}2)") (class "Default")
      (node (ref "R16") (pin "1") (pinfunction "1_1") (pintype "passive"))
      (node (ref "U5") (pin "6") (pinfunction "IM1/2_6") (pintype "passive"))
    )
    (net (code "84") (name "Net-(U5-LEDA)") (class "Default")
      (node (ref "R15") (pin "1") (pinfunction "1_1") (pintype "passive"))
      (node (ref "U5") (pin "1") (pinfunction "LEDA_1") (pintype "passive"))
    )
    (net (code "85") (name "Net-(U5-RD)") (class "Default")
      (node (ref "R18") (pin "2") (pinfunction "2_2") (pintype "passive"))
      (node (ref "U5") (pin "11") (pinfunction "RD_11") (pintype "passive"))
    )
    (net (code "86") (name "Net-(U5-RESET)") (class "Default")
      (node (ref "C15") (pin "2") (pinfunction "2_2") (pintype "passive"))
      (node (ref "R31") (pin "2") (pinfunction "2_2") (pintype "passive"))
      (node (ref "U5") (pin "7") (pinfunction "RESET_7") (pintype "passive"))
    )
    (net (code "87") (name "Net-(U5-SDA)") (class "Default")
      (node (ref "R17") (pin "2") (pinfunction "2_2") (pintype "passive"))
      (node (ref "U5") (pin "12") (pinfunction "SDA_12") (pintype "passive"))
    )
    (net (code "88") (name "Net-(U5-WR{slash}S_DC)") (class "Default")
      (node (ref "R24") (pin "2") (pinfunction "2_2") (pintype "passive"))
      (node (ref "U5") (pin "10") (pinfunction "WR/S_DC_10") (pintype "passive"))
    )
    (net (code "89") (name "Net-(U6-BYPASS)") (class "Default")
      (node (ref "C7") (pin "1") (pinfunction "1_1") (pintype "passive"))
      (node (ref "U6") (pin "2") (pinfunction "BYPASS_2") (pintype "passive"))
    )
    (net (code "90") (name "Net-(U10-RXD)") (class "Default")
      (node (ref "R33") (pin "2") (pinfunction "2_2") (pintype "passive"))
      (node (ref "U10") (pin "7") (pinfunction "RXD_7") (pintype "passive"))
    )
    (net (code "91") (name "Net-(U10-TXD)") (class "Default")
      (node (ref "R35") (pin "2") (pinfunction "2_2") (pintype "passive"))
      (node (ref "U10") (pin "6") (pinfunction "TXD_6") (pintype "passive"))
    )
    (net (code "92") (name "Net-(U10-UD+)") (class "Default")
      (node (ref "R32") (pin "1") (pinfunction "1_1") (pintype "passive"))
      (node (ref "U10") (pin "1") (pinfunction "UD+_1") (pintype "passive"))
    )
    (net (code "93") (name "Net-(U10-UD-)") (class "Default")
      (node (ref "R34") (pin "1") (pinfunction "1_1") (pintype "passive"))
      (node (ref "U10") (pin "2") (pinfunction "UD-_2") (pintype "passive"))
    )
    (net (code "94") (name "Net-(U10-V3)") (class "Default")
      (node (ref "C18") (pin "1") (pinfunction "1_1") (pintype "passive"))
      (node (ref "U10") (pin "8") (pinfunction "V3_8") (pintype "passive"))
    )
    (net (code "95") (name "V2.8") (class "Default")
      (node (ref "C13") (pin "1") (pinfunction "1_1") (pintype "passive"))
      (node (ref "C19") (pin "1") (pinfunction "1_1") (pintype "passive"))
      (node (ref "IC2") (pin "2") (pinfunction "Vout_2") (pintype "passive"))
      (node (ref "R19") (pin "2") (pinfunction "2_2") (pintype "passive"))
      (node (ref "R25") (pin "2") (pinfunction "2_2") (pintype "passive"))
      (node (ref "R27") (pin "2") (pinfunction "2_2") (pintype "passive"))
      (node (ref "U4") (pin "14") (pinfunction "DOVDD_14") (pintype "passive"))
      (node (ref "U4") (pin "21") (pinfunction "AVDD_21") (pintype "passive"))
    )
    (net (code "96") (name "VBAT") (class "Default")
      (node (ref "C24") (pin "1") (pinfunction "1_1") (pintype "passive"))
      (node (ref "C25") (pin "2") (pinfunction "2_2") (pintype "passive"))
      (node (ref "IC1") (pin "5") (pinfunction "BAT_5") (pintype "passive"))
      (node (ref "J_BAT1") (pin "2") (pinfunction "2_2") (pintype "passive"))
      (node (ref "P1") (pin "11") (pinfunction "11_11") (pintype "passive"))
      (node (ref "P2") (pin "18") (pinfunction "18_18") (pintype "passive"))
      (node (ref "Q2") (pin "3") (pinfunction "D_3") (pintype "passive"))
      (node (ref "R3") (pin "2") (pinfunction "2_2") (pintype "passive"))
    )
    (net (code "97") (name "VDD") (class "Default")
      (node (ref "C1") (pin "1") (pinfunction "1_1") (pintype "passive"))
      (node (ref "C17") (pin "1") (pinfunction "1_1") (pintype "passive"))
      (node (ref "C21") (pin "1") (pinfunction "1_1") (pintype "passive"))
      (node (ref "C3") (pin "2") (pinfunction "2_2") (pintype "passive"))
      (node (ref "C5") (pin "1") (pinfunction "1_1") (pintype "passive"))
      (node (ref "IC2") (pin "3") (pinfunction "Vin_3") (pintype "passive"))
      (node (ref "P3") (pin "6") (pinfunction "6_6") (pintype "passive"))
      (node (ref "P4") (pin "23") (pinfunction "23_23") (pintype "passive"))
      (node (ref "R10") (pin "2") (pinfunction "2_2") (pintype "passive"))
      (node (ref "R16") (pin "2") (pinfunction "2_2") (pintype "passive"))
      (node (ref "R2") (pin "1") (pinfunction "1_1") (pintype "passive"))
      (node (ref "R31") (pin "1") (pinfunction "1_1") (pintype "passive"))
      (node (ref "R8") (pin "2") (pinfunction "2_2") (pintype "passive"))
      (node (ref "R9") (pin "2") (pinfunction "2_2") (pintype "passive"))
      (node (ref "TF1") (pin "4") (pinfunction "4_4") (pintype "passive"))
      (node (ref "U2") (pin "8") (pinfunction "VCC_8") (pintype "passive"))
      (node (ref "U3") (pin "5") (pinfunction "VDD_5") (pintype "passive"))
      (node (ref "U5") (pin "4") (pinfunction "VDD_4") (pintype "passive"))
      (node (ref "U5") (pin "5") (pinfunction "IOVCC_5") (pintype "passive"))
    )
    (net (code "98") (name "VIO") (class "Default")
      (node (ref "P3") (pin "8") (pinfunction "8_8") (pintype "passive"))
      (node (ref "P4") (pin "21") (pinfunction "21_21") (pintype "passive"))
      (node (ref "U1") (pin "35") (pinfunction "V3.3_35") (pintype "passive"))
    )
    (net (code "99") (name "VPWR") (class "Default")
      (node (ref "C10") (pin "1") (pinfunction "1_1") (pintype "passive"))
      (node (ref "D3") (pin "2") (pinfunction "K_2") (pintype "passive"))
      (node (ref "L1") (pin "1") (pinfunction "1_1") (pintype "passive"))
      (node (ref "P1") (pin "1") (pinfunction "1_1") (pintype "passive"))
      (node (ref "P2") (pin "28") (pinfunction "28_28") (pintype "passive"))
      (node (ref "Q2") (pin "2") (pinfunction "S_2") (pintype "passive"))
      (node (ref "R15") (pin "2") (pinfunction "2_2") (pintype "passive"))
    )
    (net (code "100") (name "VUSB") (class "Default")
      (node (ref "C20") (pin "1") (pinfunction "1_1") (pintype "passive"))
      (node (ref "C22") (pin "2") (pinfunction "2_2") (pintype "passive"))
      (node (ref "C23") (pin "1") (pinfunction "1_1") (pintype "passive"))
      (node (ref "D1") (pin "1") (pinfunction "A_1") (pintype "passive"))
      (node (ref "D3") (pin "1") (pinfunction "A_1") (pintype "passive"))
      (node (ref "IC1") (pin "4") (pinfunction "VCC_4") (pintype "passive"))
      (node (ref "IC1") (pin "8") (pinfunction "CE_8") (pintype "passive"))
      (node (ref "J1") (pin "A4") (pinfunction "VBUS_A4") (pintype "power_in"))
      (node (ref "J1") (pin "B4") (pinfunction "VBUS_B4") (pintype "power_in"))
      (node (ref "P1") (pin "10") (pinfunction "10_10") (pintype "passive"))
      (node (ref "P2") (pin "19") (pinfunction "19_19") (pintype "passive"))
      (node (ref "Q2") (pin "1") (pinfunction "G_1") (pintype "passive"))
      (node (ref "R39") (pin "2") (pinfunction "2_2") (pintype "passive"))
      (node (ref "R4") (pin "2") (pinfunction "2_2") (pintype "passive"))
      (node (ref "R40") (pin "2") (pinfunction "2_2") (pintype "passive"))
      (node (ref "U10") (pin "5") (pinfunction "VCC_5") (pintype "passive"))
    )
    (net (code "101") (name "unconnected-(J1-CC1-PadA5)") (class "Default")
      (node (ref "J1") (pin "A5") (pinfunction "CC1_A5") (pintype "passive+no_connect"))
    )
    (net (code "102") (name "unconnected-(J1-CC2-PadB5)") (class "Default")
      (node (ref "J1") (pin "B5") (pinfunction "CC2_B5") (pintype "passive+no_connect"))
    )
    (net (code "103") (name "unconnected-(J1-SBU1-PadA8)") (class "Default")
      (node (ref "J1") (pin "A8") (pinfunction "SBU1_A8") (pintype "passive+no_connect"))
    )
    (net (code "104") (name "unconnected-(J1-SBU2-PadB8)") (class "Default")
      (node (ref "J1") (pin "B8") (pinfunction "SBU2_B8") (pintype "passive+no_connect"))
    )
    (net (code "105") (name "unconnected-(R18-Pad1)") (class "Default")
      (node (ref "R18") (pin "1") (pinfunction "1_1") (pintype "passive"))
    )
    (net (code "106") (name "unconnected-(R38-Pad1)") (class "Default")
      (node (ref "R38") (pin "1") (pinfunction "1_1") (pintype "passive"))
    )
    (net (code "107") (name "unconnected-(R38-Pad2)") (class "Default")
      (node (ref "R38") (pin "2") (pinfunction "2_2") (pintype "passive"))
    )
    (net (code "108") (name "unconnected-(TF1-Pad1)") (class "Default")
      (node (ref "TF1") (pin "1") (pinfunction "1_1") (pintype "passive+no_connect"))
    )
    (net (code "109") (name "unconnected-(TF1-Pad2)") (class "Default")
      (node (ref "TF1") (pin "2") (pinfunction "2_2") (pintype "passive+no_connect"))
    )
    (net (code "110") (name "unconnected-(TF1-Pad8)") (class "Default")
      (node (ref "TF1") (pin "8") (pinfunction "8_8") (pintype "passive+no_connect"))
    )
    (net (code "111") (name "unconnected-(TF1-Pad9)") (class "Default")
      (node (ref "TF1") (pin "9") (pinfunction "9_9") (pintype "passive"))
    )
    (net (code "112") (name "unconnected-(U3-ALE-Pad3)") (class "Default")
      (node (ref "U3") (pin "3") (pinfunction "ALE_3") (pintype "passive"))
    )
    (net (code "113") (name "unconnected-(U3-RST-Pad6)") (class "Default")
      (node (ref "U3") (pin "6") (pinfunction "RST_6") (pintype "passive"))
    )
    (net (code "114") (name "unconnected-(U4-NC-Pad1)") (class "Default")
      (node (ref "U4") (pin "1") (pinfunction "NC_1") (pintype "passive+no_connect"))
    )
    (net (code "115") (name "unconnected-(U4-NC-Pad2)") (class "Default")
      (node (ref "U4") (pin "2") (pinfunction "NC_2") (pintype "passive+no_connect"))
    )
    (net (code "116") (name "unconnected-(U4-STRB-Pad24)") (class "Default")
      (node (ref "U4") (pin "24") (pinfunction "STRB_24") (pintype "passive"))
    )
    (net (code "117") (name "unconnected-(U5-DB0-Pad13)") (class "Default")
      (node (ref "U5") (pin "13") (pinfunction "DB0_13") (pintype "passive+no_connect"))
    )
    (net (code "118") (name "unconnected-(U5-DB1-Pad14)") (class "Default")
      (node (ref "U5") (pin "14") (pinfunction "DB1_14") (pintype "passive+no_connect"))
    )
    (net (code "119") (name "unconnected-(U5-DB2-Pad15)") (class "Default")
      (node (ref "U5") (pin "15") (pinfunction "DB2_15") (pintype "passive+no_connect"))
    )
    (net (code "120") (name "unconnected-(U5-DB3-Pad16)") (class "Default")
      (node (ref "U5") (pin "16") (pinfunction "DB3_16") (pintype "passive+no_connect"))
    )
    (net (code "121") (name "unconnected-(U5-DB4-Pad17)") (class "Default")
      (node (ref "U5") (pin "17") (pinfunction "DB4_17") (pintype "passive+no_connect"))
    )
    (net (code "122") (name "unconnected-(U5-DB5-Pad18)") (class "Default")
      (node (ref "U5") (pin "18") (pinfunction "DB5_18") (pintype "passive+no_connect"))
    )
    (net (code "123") (name "unconnected-(U5-DB6-Pad19)") (class "Default")
      (node (ref "U5") (pin "19") (pinfunction "DB6_19") (pintype "passive+no_connect"))
    )
    (net (code "124") (name "unconnected-(U5-DB7-Pad20)") (class "Default")
      (node (ref "U5") (pin "20") (pinfunction "DB7_20") (pintype "passive+no_connect"))
    )
    (net (code "125") (name "unconnected-(U5-NC-Pad22)") (class "Default")
      (node (ref "U5") (pin "22") (pinfunction "NC_22") (pintype "passive+no_connect"))
    )
    (net (code "126") (name "unconnected-(U5-TE-Pad21)") (class "Default")
      (node (ref "U5") (pin "21") (pinfunction "TE_21") (pintype "passive+no_connect"))
    )
    (net (code "127") (name "unconnected-(U10-RTS-Pad4)") (class "Default")
      (node (ref "U10") (pin "4") (pinfunction "RTS_4") (pintype "passive+no_connect"))
    )
  )
)
